# H05.net
KiCad netlist of a schematic drawn in EAGLE
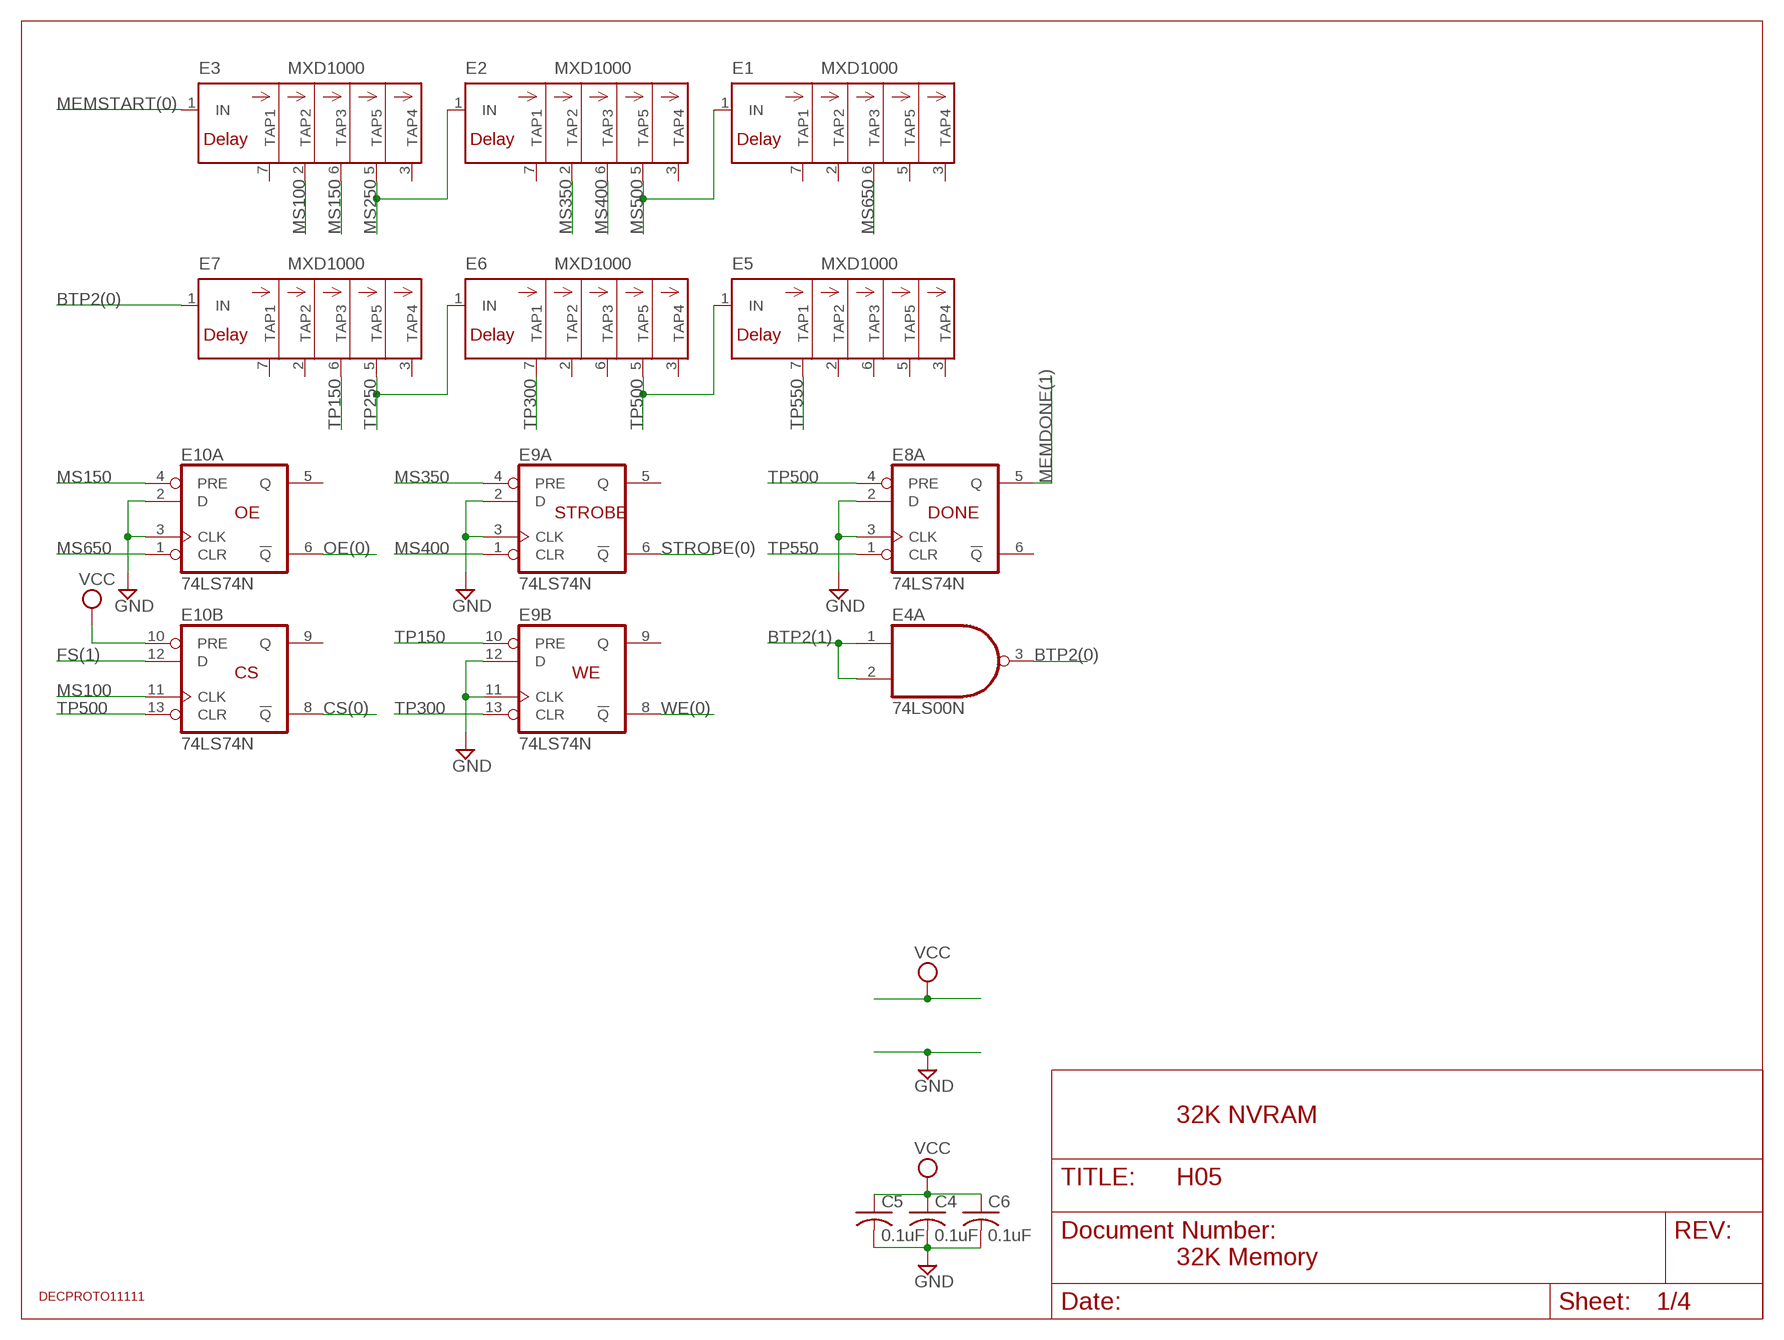
[diagram p0: schematic, sheet 1]
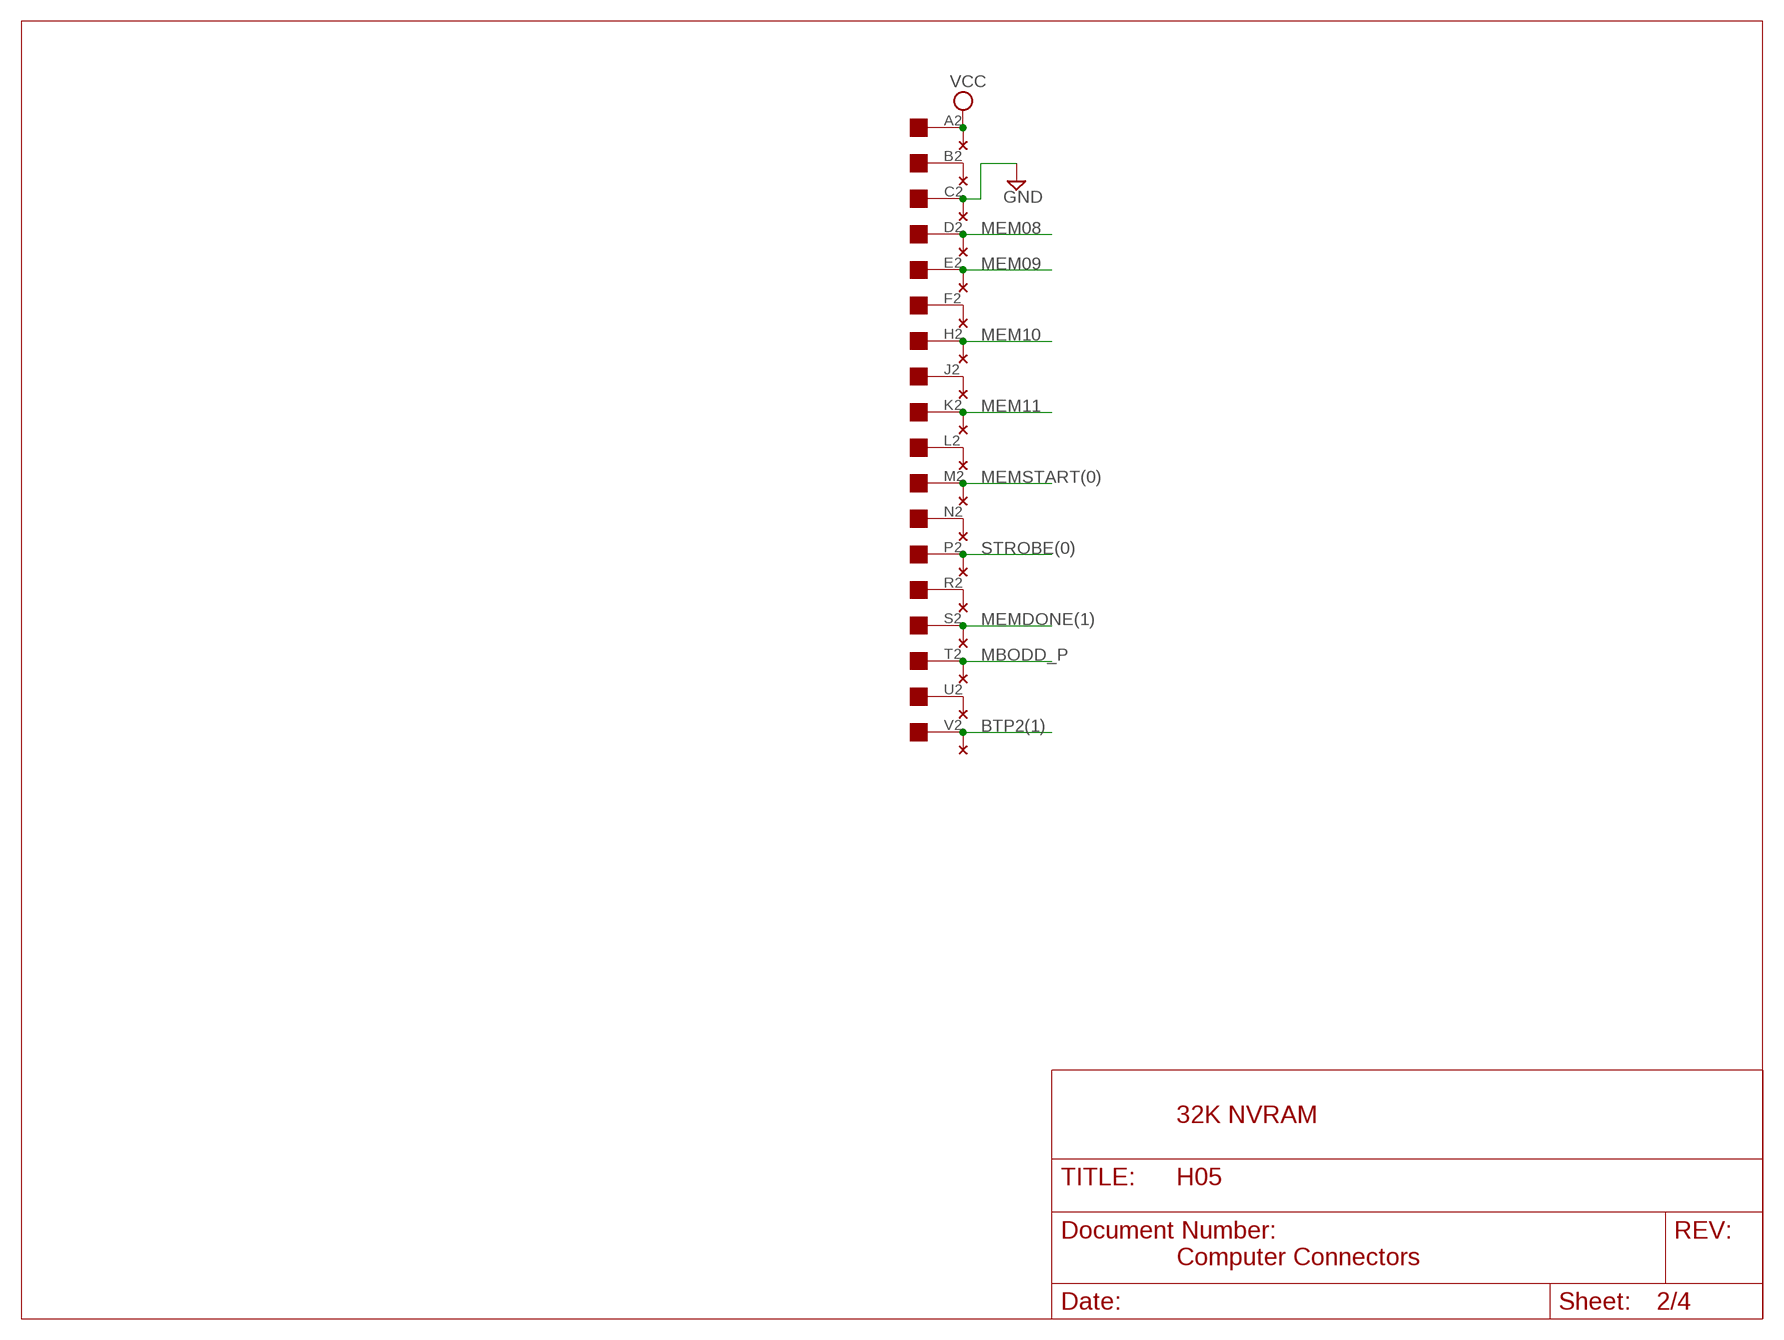
[diagram p1: schematic, sheet 2]
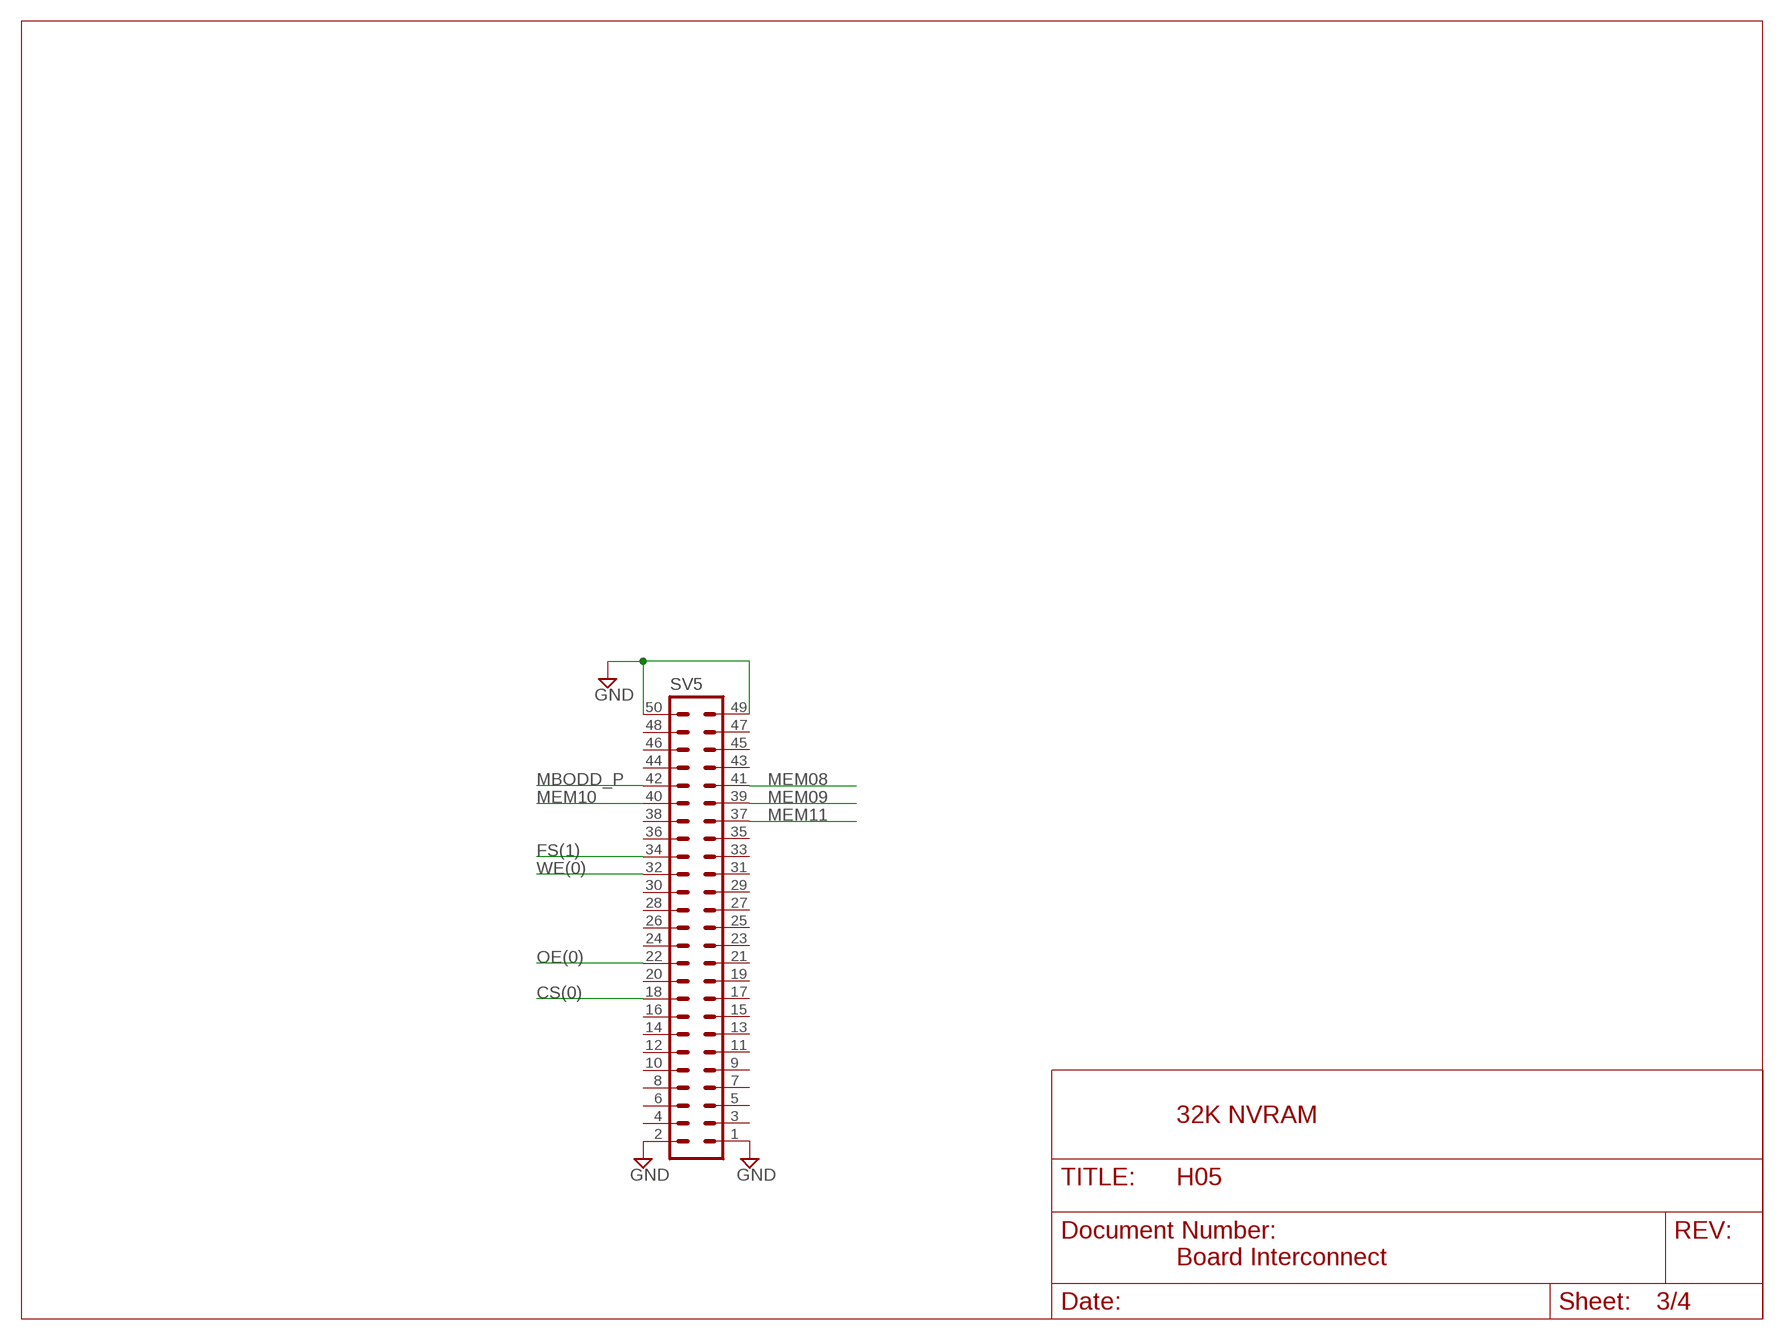
[diagram p2: schematic, sheet 3]
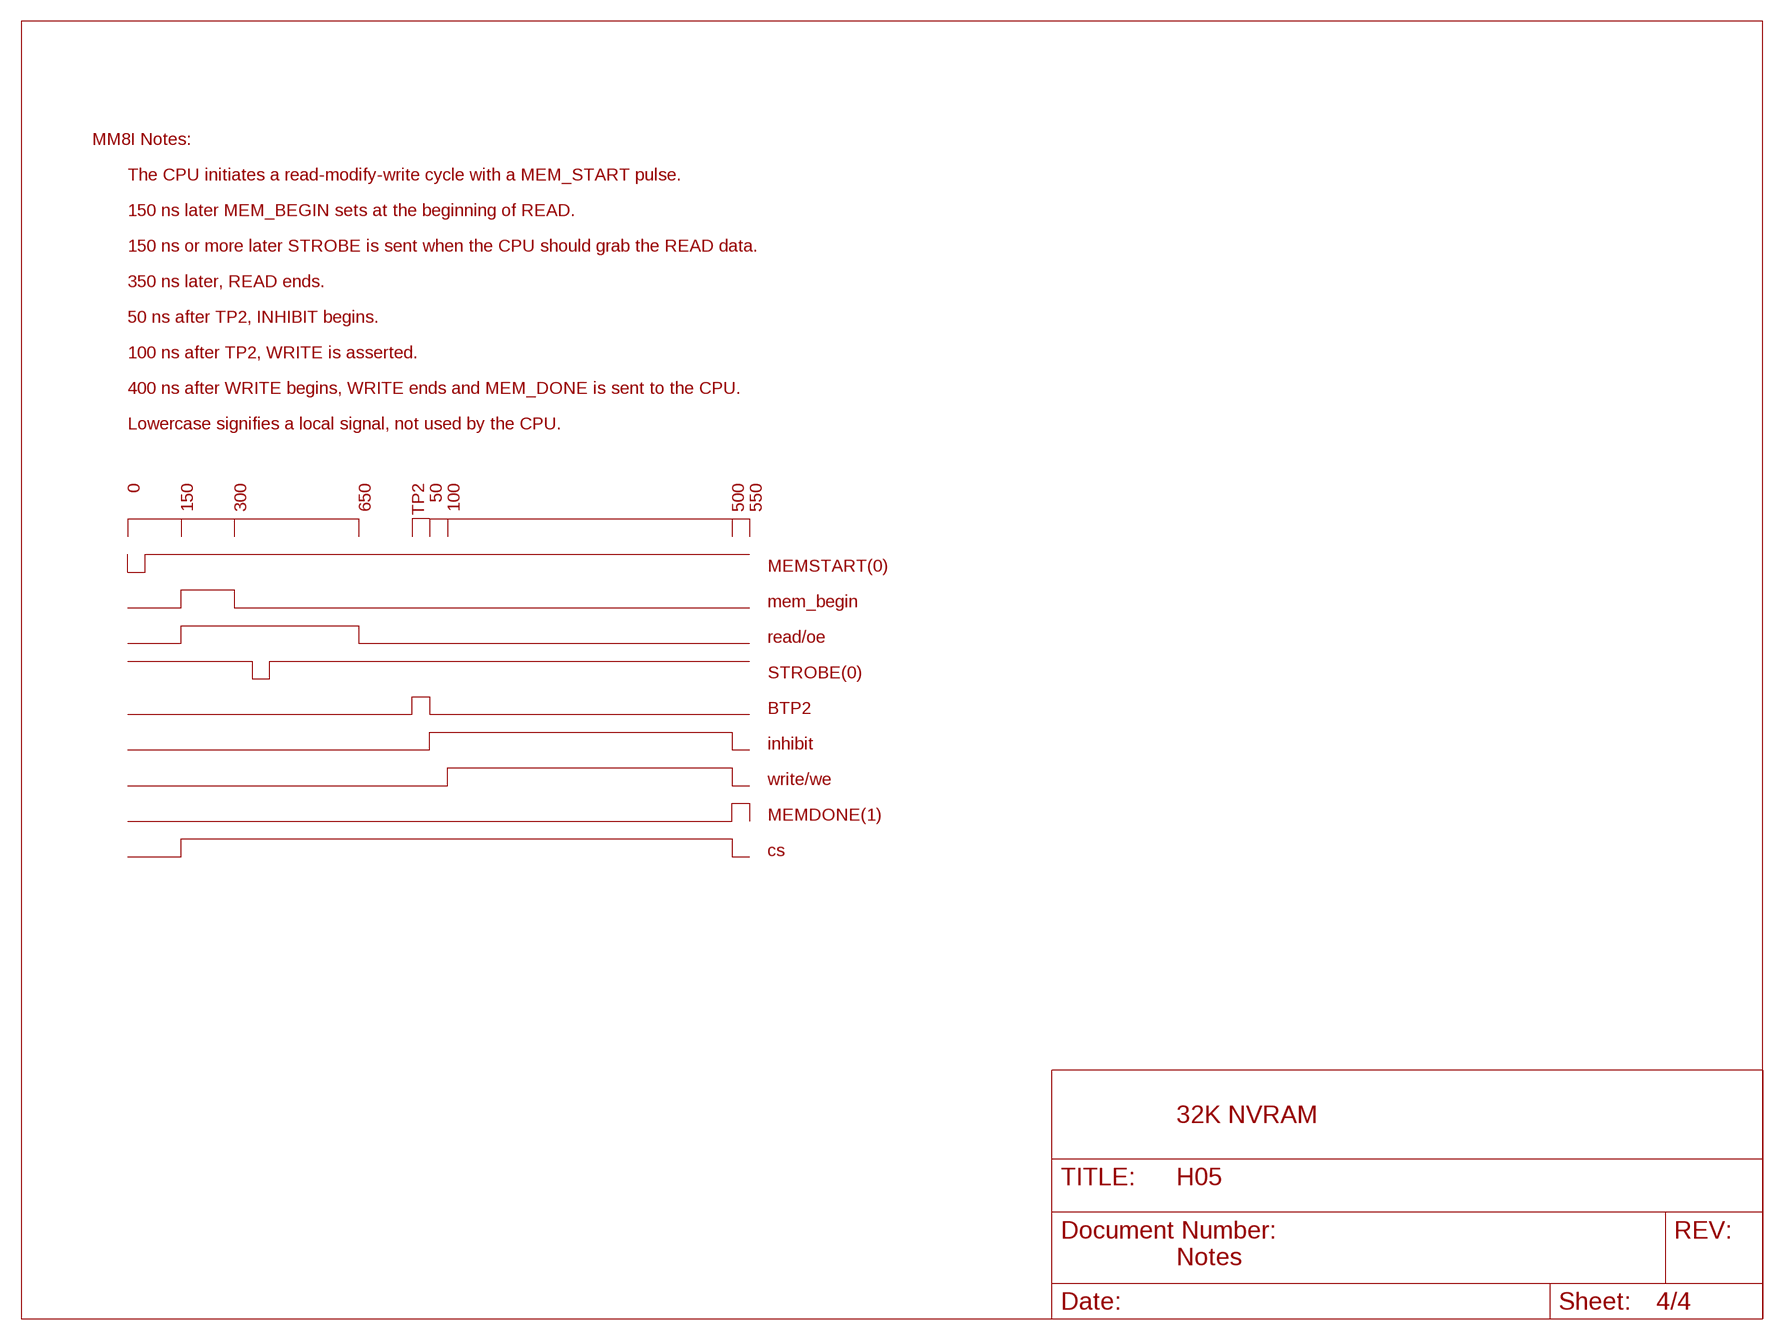
[diagram p3: schematic, sheet 4]

(export (version "E")
  (design (tool "Eeschema 10.0.6"))
  (components
    (comp (ref "H05")
      (value "EDGE-1")
      (footprint "eagle-import:EDGE-CON1")
      (libsource (lib "eagle-import") (part "EDGE-1"))
    )
    (comp (ref "U$5")
      (value "THRU-HOLE2")
      (footprint "eagle-import:THRU-HOLEB")
      (libsource (lib "eagle-import") (part "THRU-HOLE2"))
    )
    (comp (ref "C4")
      (value "0.1uF")
      (footprint "eagle-import:C050-025X075")
      (libsource (lib "eagle-import") (part "C-US050-025X075"))
    )
    (comp (ref "C5")
      (value "0.1uF")
      (footprint "eagle-import:C050-025X075")
      (libsource (lib "eagle-import") (part "C-US050-025X075"))
    )
    (comp (ref "C6")
      (value "0.1uF")
      (footprint "eagle-import:C050-025X075")
      (libsource (lib "eagle-import") (part "C-US050-025X075"))
    )
    (comp (ref "E1")
      (value "MXD1000")
      (footprint "eagle-import:DIL08")
      (libsource (lib "eagle-import") (part "MXD1000"))
    )
    (comp (ref "E2")
      (value "MXD1000")
      (footprint "eagle-import:DIL08")
      (libsource (lib "eagle-import") (part "MXD1000"))
    )
    (comp (ref "E3")
      (value "MXD1000")
      (footprint "eagle-import:DIL08")
      (libsource (lib "eagle-import") (part "MXD1000"))
    )
    (comp (ref "E4")
      (value "74LS00N")
      (footprint "eagle-import:DIL14")
      (libsource (lib "eagle-import") (part "7400NLS"))
    )
    (comp (ref "E5")
      (value "MXD1000")
      (footprint "eagle-import:DIL08")
      (libsource (lib "eagle-import") (part "MXD1000"))
    )
    (comp (ref "E6")
      (value "MXD1000")
      (footprint "eagle-import:DIL08")
      (libsource (lib "eagle-import") (part "MXD1000"))
    )
    (comp (ref "E7")
      (value "MXD1000")
      (footprint "eagle-import:DIL08")
      (libsource (lib "eagle-import") (part "MXD1000"))
    )
    (comp (ref "E8")
      (value "74LS74N")
      (footprint "eagle-import:DIL14")
      (libsource (lib "eagle-import") (part "7474NLS"))
    )
    (comp (ref "E9")
      (value "74LS74N")
      (footprint "eagle-import:DIL14")
      (libsource (lib "eagle-import") (part "7474NLS"))
    )
    (comp (ref "E10")
      (value "74LS74N")
      (footprint "eagle-import:DIL14")
      (libsource (lib "eagle-import") (part "7474NLS"))
    )
    (comp (ref "U$6")
      (value "DECPROTO11111")
      (footprint "eagle-import:DECPROTO11111")
      (libsource (lib "eagle-import") (part "DECPROTO11111"))
    )
    (comp (ref "SV5")
      (value "ML50L")
      (footprint "eagle-import:ML50L")
      (libsource (lib "eagle-import") (part "ML50L"))
    )
  )
  (nets
    (net (code "1") (name "BTP2(0)") (class "Default")
      (node (ref "E4") (pin "3") (pinfunction "O_3") (pintype "output"))
      (node (ref "E7") (pin "1") (pinfunction "IN_1") (pintype "input"))
    )
    (net (code "2") (name "BTP2(1)") (class "Default")
      (node (ref "E4") (pin "1") (pinfunction "I0_1") (pintype "input"))
      (node (ref "E4") (pin "2") (pinfunction "I1_2") (pintype "input"))
      (node (ref "H05") (pin "V2") (pinfunction "1_V2") (pintype "bidirectional"))
      (node (ref "U$5") (pin "V2") (pinfunction "P$1_V2") (pintype "passive"))
    )
    (net (code "3") (name "CS(0)") (class "Default")
      (node (ref "E10") (pin "8") (pinfunction "~{Q}_8") (pintype "output"))
      (node (ref "SV5") (pin "18") (pinfunction "18_18") (pintype "passive"))
    )
    (net (code "4") (name "FS(1)") (class "Default")
      (node (ref "E10") (pin "12") (pinfunction "D_12") (pintype "input"))
      (node (ref "SV5") (pin "34") (pinfunction "34_34") (pintype "passive"))
    )
    (net (code "5") (name "GND") (class "Default")
      (node (ref "C4") (pin "2") (pinfunction "2_2") (pintype "passive"))
      (node (ref "C5") (pin "2") (pinfunction "2_2") (pintype "passive"))
      (node (ref "C6") (pin "2") (pinfunction "2_2") (pintype "passive"))
      (node (ref "E10") (pin "2") (pinfunction "D_2") (pintype "input"))
      (node (ref "E10") (pin "3") (pinfunction "CLK_3") (pintype "input"))
      (node (ref "E8") (pin "2") (pinfunction "D_2") (pintype "input"))
      (node (ref "E8") (pin "3") (pinfunction "CLK_3") (pintype "input"))
      (node (ref "E9") (pin "11") (pinfunction "CLK_11") (pintype "input"))
      (node (ref "E9") (pin "12") (pinfunction "D_12") (pintype "input"))
      (node (ref "E9") (pin "2") (pinfunction "D_2") (pintype "input"))
      (node (ref "E9") (pin "3") (pinfunction "CLK_3") (pintype "input"))
      (node (ref "H05") (pin "C2") (pinfunction "1_C2") (pintype "bidirectional"))
      (node (ref "SV5") (pin "1") (pinfunction "1_1") (pintype "passive"))
      (node (ref "SV5") (pin "2") (pinfunction "2_2") (pintype "passive"))
      (node (ref "SV5") (pin "49") (pinfunction "49_49") (pintype "passive"))
      (node (ref "SV5") (pin "50") (pinfunction "50_50") (pintype "passive"))
      (node (ref "U$5") (pin "C2") (pinfunction "P$1_C2") (pintype "passive"))
    )
    (net (code "6") (name "MBODD_P") (class "Default")
      (node (ref "H05") (pin "T2") (pinfunction "1_T2") (pintype "bidirectional"))
      (node (ref "SV5") (pin "42") (pinfunction "42_42") (pintype "passive"))
      (node (ref "U$5") (pin "T2") (pinfunction "P$1_T2") (pintype "passive"))
    )
    (net (code "7") (name "MEM08") (class "Default")
      (node (ref "H05") (pin "D2") (pinfunction "1_D2") (pintype "bidirectional"))
      (node (ref "SV5") (pin "41") (pinfunction "41_41") (pintype "passive"))
      (node (ref "U$5") (pin "D2") (pinfunction "P$1_D2") (pintype "passive"))
    )
    (net (code "8") (name "MEM09") (class "Default")
      (node (ref "H05") (pin "E2") (pinfunction "1_E2") (pintype "bidirectional"))
      (node (ref "SV5") (pin "39") (pinfunction "39_39") (pintype "passive"))
      (node (ref "U$5") (pin "E2") (pinfunction "P$1_E2") (pintype "passive"))
    )
    (net (code "9") (name "MEM10") (class "Default")
      (node (ref "H05") (pin "H2") (pinfunction "1_H2") (pintype "bidirectional"))
      (node (ref "SV5") (pin "40") (pinfunction "40_40") (pintype "passive"))
      (node (ref "U$5") (pin "H2") (pinfunction "P$1_H2") (pintype "passive"))
    )
    (net (code "10") (name "MEM11") (class "Default")
      (node (ref "H05") (pin "K2") (pinfunction "1_K2") (pintype "bidirectional"))
      (node (ref "SV5") (pin "37") (pinfunction "37_37") (pintype "passive"))
      (node (ref "U$5") (pin "K2") (pinfunction "P$1_K2") (pintype "passive"))
    )
    (net (code "11") (name "MEMDONE(1)") (class "Default")
      (node (ref "E8") (pin "5") (pinfunction "Q_5") (pintype "output"))
      (node (ref "H05") (pin "S2") (pinfunction "1_S2") (pintype "bidirectional"))
      (node (ref "U$5") (pin "S2") (pinfunction "P$1_S2") (pintype "passive"))
    )
    (net (code "12") (name "MEMSTART(0)") (class "Default")
      (node (ref "E3") (pin "1") (pinfunction "IN_1") (pintype "input"))
      (node (ref "H05") (pin "M2") (pinfunction "1_M2") (pintype "bidirectional"))
      (node (ref "U$5") (pin "M2") (pinfunction "P$1_M2") (pintype "passive"))
    )
    (net (code "13") (name "MS100") (class "Default")
      (node (ref "E10") (pin "11") (pinfunction "CLK_11") (pintype "input"))
      (node (ref "E3") (pin "2") (pinfunction "TAP2_2") (pintype "output"))
    )
    (net (code "14") (name "MS150") (class "Default")
      (node (ref "E10") (pin "4") (pinfunction "PRE_4") (pintype "input"))
      (node (ref "E3") (pin "6") (pinfunction "TAP3_6") (pintype "output"))
    )
    (net (code "15") (name "MS250") (class "Default")
      (node (ref "E2") (pin "1") (pinfunction "IN_1") (pintype "input"))
      (node (ref "E3") (pin "5") (pinfunction "TAP5_5") (pintype "output"))
    )
    (net (code "16") (name "MS350") (class "Default")
      (node (ref "E2") (pin "2") (pinfunction "TAP2_2") (pintype "output"))
      (node (ref "E9") (pin "4") (pinfunction "PRE_4") (pintype "input"))
    )
    (net (code "17") (name "MS400") (class "Default")
      (node (ref "E2") (pin "6") (pinfunction "TAP3_6") (pintype "output"))
      (node (ref "E9") (pin "1") (pinfunction "CLR_1") (pintype "input"))
    )
    (net (code "18") (name "MS500") (class "Default")
      (node (ref "E1") (pin "1") (pinfunction "IN_1") (pintype "input"))
      (node (ref "E2") (pin "5") (pinfunction "TAP5_5") (pintype "output"))
    )
    (net (code "19") (name "MS650") (class "Default")
      (node (ref "E1") (pin "6") (pinfunction "TAP3_6") (pintype "output"))
      (node (ref "E10") (pin "1") (pinfunction "CLR_1") (pintype "input"))
    )
    (net (code "20") (name "Net-(H05B-1)") (class "Default")
      (node (ref "H05") (pin "B2") (pinfunction "1_B2") (pintype "bidirectional"))
      (node (ref "U$5") (pin "B2") (pinfunction "P$1_B2") (pintype "passive"))
    )
    (net (code "21") (name "Net-(H05F-1)") (class "Default")
      (node (ref "H05") (pin "F2") (pinfunction "1_F2") (pintype "bidirectional"))
      (node (ref "U$5") (pin "F2") (pinfunction "P$1_F2") (pintype "passive"))
    )
    (net (code "22") (name "Net-(H05H-1)") (class "Default")
      (node (ref "H05") (pin "J2") (pinfunction "1_J2") (pintype "bidirectional"))
      (node (ref "U$5") (pin "J2") (pinfunction "P$1_J2") (pintype "passive"))
    )
    (net (code "23") (name "Net-(H05J-1)") (class "Default")
      (node (ref "H05") (pin "L2") (pinfunction "1_L2") (pintype "bidirectional"))
      (node (ref "U$5") (pin "L2") (pinfunction "P$1_L2") (pintype "passive"))
    )
    (net (code "24") (name "Net-(H05L-1)") (class "Default")
      (node (ref "H05") (pin "N2") (pinfunction "1_N2") (pintype "bidirectional"))
      (node (ref "U$5") (pin "N2") (pinfunction "P$1_N2") (pintype "passive"))
    )
    (net (code "25") (name "Net-(H05N-1)") (class "Default")
      (node (ref "H05") (pin "R2") (pinfunction "1_R2") (pintype "bidirectional"))
      (node (ref "U$5") (pin "R2") (pinfunction "P$1_R2") (pintype "passive"))
    )
    (net (code "26") (name "Net-(H05Q-1)") (class "Default")
      (node (ref "H05") (pin "U2") (pinfunction "1_U2") (pintype "bidirectional"))
      (node (ref "U$5") (pin "U2") (pinfunction "P$1_U2") (pintype "passive"))
    )
    (net (code "27") (name "OE(0)") (class "Default")
      (node (ref "E10") (pin "6") (pinfunction "~{Q}_6") (pintype "output"))
      (node (ref "SV5") (pin "22") (pinfunction "22_22") (pintype "passive"))
    )
    (net (code "28") (name "STROBE(0)") (class "Default")
      (node (ref "E9") (pin "6") (pinfunction "~{Q}_6") (pintype "output"))
      (node (ref "H05") (pin "P2") (pinfunction "1_P2") (pintype "bidirectional"))
      (node (ref "U$5") (pin "P2") (pinfunction "P$1_P2") (pintype "passive"))
    )
    (net (code "29") (name "TP150") (class "Default")
      (node (ref "E7") (pin "6") (pinfunction "TAP3_6") (pintype "output"))
      (node (ref "E9") (pin "10") (pinfunction "PRE_10") (pintype "input"))
    )
    (net (code "30") (name "TP250") (class "Default")
      (node (ref "E6") (pin "1") (pinfunction "IN_1") (pintype "input"))
      (node (ref "E7") (pin "5") (pinfunction "TAP5_5") (pintype "output"))
    )
    (net (code "31") (name "TP300") (class "Default")
      (node (ref "E6") (pin "7") (pinfunction "TAP1_7") (pintype "output"))
      (node (ref "E9") (pin "13") (pinfunction "CLR_13") (pintype "input"))
    )
    (net (code "32") (name "TP500") (class "Default")
      (node (ref "E10") (pin "13") (pinfunction "CLR_13") (pintype "input"))
      (node (ref "E5") (pin "1") (pinfunction "IN_1") (pintype "input"))
      (node (ref "E6") (pin "5") (pinfunction "TAP5_5") (pintype "output"))
      (node (ref "E8") (pin "4") (pinfunction "PRE_4") (pintype "input"))
    )
    (net (code "33") (name "TP550") (class "Default")
      (node (ref "E5") (pin "7") (pinfunction "TAP1_7") (pintype "output"))
      (node (ref "E8") (pin "1") (pinfunction "CLR_1") (pintype "input"))
    )
    (net (code "34") (name "VCC") (class "Default")
      (node (ref "C4") (pin "1") (pinfunction "1_1") (pintype "passive"))
      (node (ref "C5") (pin "1") (pinfunction "1_1") (pintype "passive"))
      (node (ref "C6") (pin "1") (pinfunction "1_1") (pintype "passive"))
      (node (ref "E10") (pin "10") (pinfunction "PRE_10") (pintype "input"))
      (node (ref "H05") (pin "A2") (pinfunction "1_A2") (pintype "bidirectional"))
      (node (ref "U$5") (pin "A2") (pinfunction "P$1_A2") (pintype "passive"))
    )
    (net (code "35") (name "WE(0)") (class "Default")
      (node (ref "E9") (pin "8") (pinfunction "~{Q}_8") (pintype "output"))
      (node (ref "SV5") (pin "32") (pinfunction "32_32") (pintype "passive"))
    )
    (net (code "36") (name "unconnected-(E1A-TAP1-Pad7)") (class "Default")
      (node (ref "E1") (pin "7") (pinfunction "TAP1_7") (pintype "output"))
    )
    (net (code "37") (name "unconnected-(E1A-TAP2-Pad2)") (class "Default")
      (node (ref "E1") (pin "2") (pinfunction "TAP2_2") (pintype "output"))
    )
    (net (code "38") (name "unconnected-(E1A-TAP4-Pad3)") (class "Default")
      (node (ref "E1") (pin "3") (pinfunction "TAP4_3") (pintype "output"))
    )
    (net (code "39") (name "unconnected-(E1A-TAP5-Pad5)") (class "Default")
      (node (ref "E1") (pin "5") (pinfunction "TAP5_5") (pintype "output"))
    )
    (net (code "40") (name "unconnected-(E2A-TAP1-Pad7)") (class "Default")
      (node (ref "E2") (pin "7") (pinfunction "TAP1_7") (pintype "output"))
    )
    (net (code "41") (name "unconnected-(E2A-TAP4-Pad3)") (class "Default")
      (node (ref "E2") (pin "3") (pinfunction "TAP4_3") (pintype "output"))
    )
    (net (code "42") (name "unconnected-(E3A-TAP1-Pad7)") (class "Default")
      (node (ref "E3") (pin "7") (pinfunction "TAP1_7") (pintype "output"))
    )
    (net (code "43") (name "unconnected-(E3A-TAP4-Pad3)") (class "Default")
      (node (ref "E3") (pin "3") (pinfunction "TAP4_3") (pintype "output"))
    )
    (net (code "44") (name "unconnected-(E5A-TAP2-Pad2)") (class "Default")
      (node (ref "E5") (pin "2") (pinfunction "TAP2_2") (pintype "output"))
    )
    (net (code "45") (name "unconnected-(E5A-TAP3-Pad6)") (class "Default")
      (node (ref "E5") (pin "6") (pinfunction "TAP3_6") (pintype "output"))
    )
    (net (code "46") (name "unconnected-(E5A-TAP4-Pad3)") (class "Default")
      (node (ref "E5") (pin "3") (pinfunction "TAP4_3") (pintype "output"))
    )
    (net (code "47") (name "unconnected-(E5A-TAP5-Pad5)") (class "Default")
      (node (ref "E5") (pin "5") (pinfunction "TAP5_5") (pintype "output"))
    )
    (net (code "48") (name "unconnected-(E6A-TAP2-Pad2)") (class "Default")
      (node (ref "E6") (pin "2") (pinfunction "TAP2_2") (pintype "output"))
    )
    (net (code "49") (name "unconnected-(E6A-TAP3-Pad6)") (class "Default")
      (node (ref "E6") (pin "6") (pinfunction "TAP3_6") (pintype "output"))
    )
    (net (code "50") (name "unconnected-(E6A-TAP4-Pad3)") (class "Default")
      (node (ref "E6") (pin "3") (pinfunction "TAP4_3") (pintype "output"))
    )
    (net (code "51") (name "unconnected-(E7A-TAP1-Pad7)") (class "Default")
      (node (ref "E7") (pin "7") (pinfunction "TAP1_7") (pintype "output"))
    )
    (net (code "52") (name "unconnected-(E7A-TAP2-Pad2)") (class "Default")
      (node (ref "E7") (pin "2") (pinfunction "TAP2_2") (pintype "output"))
    )
    (net (code "53") (name "unconnected-(E7A-TAP4-Pad3)") (class "Default")
      (node (ref "E7") (pin "3") (pinfunction "TAP4_3") (pintype "output"))
    )
    (net (code "54") (name "unconnected-(E8A-~{Q}-Pad6)") (class "Default")
      (node (ref "E8") (pin "6") (pinfunction "~{Q}_6") (pintype "output"))
    )
    (net (code "55") (name "unconnected-(E9A-Q-Pad5)") (class "Default")
      (node (ref "E9") (pin "5") (pinfunction "Q_5") (pintype "output"))
    )
    (net (code "56") (name "unconnected-(E9B-Q-Pad9)") (class "Default")
      (node (ref "E9") (pin "9") (pinfunction "Q_9") (pintype "output"))
    )
    (net (code "57") (name "unconnected-(E10A-Q-Pad5)") (class "Default")
      (node (ref "E10") (pin "5") (pinfunction "Q_5") (pintype "output"))
    )
    (net (code "58") (name "unconnected-(E10B-Q-Pad9)") (class "Default")
      (node (ref "E10") (pin "9") (pinfunction "Q_9") (pintype "output"))
    )
    (net (code "59") (name "unconnected-(SV5-Pad3)") (class "Default")
      (node (ref "SV5") (pin "3") (pinfunction "3_3") (pintype "passive"))
    )
    (net (code "60") (name "unconnected-(SV5-Pad4)") (class "Default")
      (node (ref "SV5") (pin "4") (pinfunction "4_4") (pintype "passive"))
    )
    (net (code "61") (name "unconnected-(SV5-Pad5)") (class "Default")
      (node (ref "SV5") (pin "5") (pinfunction "5_5") (pintype "passive"))
    )
    (net (code "62") (name "unconnected-(SV5-Pad6)") (class "Default")
      (node (ref "SV5") (pin "6") (pinfunction "6_6") (pintype "passive"))
    )
    (net (code "63") (name "unconnected-(SV5-Pad7)") (class "Default")
      (node (ref "SV5") (pin "7") (pinfunction "7_7") (pintype "passive"))
    )
    (net (code "64") (name "unconnected-(SV5-Pad8)") (class "Default")
      (node (ref "SV5") (pin "8") (pinfunction "8_8") (pintype "passive"))
    )
    (net (code "65") (name "unconnected-(SV5-Pad9)") (class "Default")
      (node (ref "SV5") (pin "9") (pinfunction "9_9") (pintype "passive"))
    )
    (net (code "66") (name "unconnected-(SV5-Pad10)") (class "Default")
      (node (ref "SV5") (pin "10") (pinfunction "10_10") (pintype "passive"))
    )
    (net (code "67") (name "unconnected-(SV5-Pad11)") (class "Default")
      (node (ref "SV5") (pin "11") (pinfunction "11_11") (pintype "passive"))
    )
    (net (code "68") (name "unconnected-(SV5-Pad12)") (class "Default")
      (node (ref "SV5") (pin "12") (pinfunction "12_12") (pintype "passive"))
    )
    (net (code "69") (name "unconnected-(SV5-Pad13)") (class "Default")
      (node (ref "SV5") (pin "13") (pinfunction "13_13") (pintype "passive"))
    )
    (net (code "70") (name "unconnected-(SV5-Pad14)") (class "Default")
      (node (ref "SV5") (pin "14") (pinfunction "14_14") (pintype "passive"))
    )
    (net (code "71") (name "unconnected-(SV5-Pad15)") (class "Default")
      (node (ref "SV5") (pin "15") (pinfunction "15_15") (pintype "passive"))
    )
    (net (code "72") (name "unconnected-(SV5-Pad16)") (class "Default")
      (node (ref "SV5") (pin "16") (pinfunction "16_16") (pintype "passive"))
    )
    (net (code "73") (name "unconnected-(SV5-Pad17)") (class "Default")
      (node (ref "SV5") (pin "17") (pinfunction "17_17") (pintype "passive"))
    )
    (net (code "74") (name "unconnected-(SV5-Pad19)") (class "Default")
      (node (ref "SV5") (pin "19") (pinfunction "19_19") (pintype "passive"))
    )
    (net (code "75") (name "unconnected-(SV5-Pad20)") (class "Default")
      (node (ref "SV5") (pin "20") (pinfunction "20_20") (pintype "passive"))
    )
    (net (code "76") (name "unconnected-(SV5-Pad21)") (class "Default")
      (node (ref "SV5") (pin "21") (pinfunction "21_21") (pintype "passive"))
    )
    (net (code "77") (name "unconnected-(SV5-Pad23)") (class "Default")
      (node (ref "SV5") (pin "23") (pinfunction "23_23") (pintype "passive"))
    )
    (net (code "78") (name "unconnected-(SV5-Pad24)") (class "Default")
      (node (ref "SV5") (pin "24") (pinfunction "24_24") (pintype "passive"))
    )
    (net (code "79") (name "unconnected-(SV5-Pad25)") (class "Default")
      (node (ref "SV5") (pin "25") (pinfunction "25_25") (pintype "passive"))
    )
    (net (code "80") (name "unconnected-(SV5-Pad26)") (class "Default")
      (node (ref "SV5") (pin "26") (pinfunction "26_26") (pintype "passive"))
    )
    (net (code "81") (name "unconnected-(SV5-Pad27)") (class "Default")
      (node (ref "SV5") (pin "27") (pinfunction "27_27") (pintype "passive"))
    )
    (net (code "82") (name "unconnected-(SV5-Pad28)") (class "Default")
      (node (ref "SV5") (pin "28") (pinfunction "28_28") (pintype "passive"))
    )
    (net (code "83") (name "unconnected-(SV5-Pad29)") (class "Default")
      (node (ref "SV5") (pin "29") (pinfunction "29_29") (pintype "passive"))
    )
    (net (code "84") (name "unconnected-(SV5-Pad30)") (class "Default")
      (node (ref "SV5") (pin "30") (pinfunction "30_30") (pintype "passive"))
    )
    (net (code "85") (name "unconnected-(SV5-Pad31)") (class "Default")
      (node (ref "SV5") (pin "31") (pinfunction "31_31") (pintype "passive"))
    )
    (net (code "86") (name "unconnected-(SV5-Pad33)") (class "Default")
      (node (ref "SV5") (pin "33") (pinfunction "33_33") (pintype "passive"))
    )
    (net (code "87") (name "unconnected-(SV5-Pad35)") (class "Default")
      (node (ref "SV5") (pin "35") (pinfunction "35_35") (pintype "passive"))
    )
    (net (code "88") (name "unconnected-(SV5-Pad36)") (class "Default")
      (node (ref "SV5") (pin "36") (pinfunction "36_36") (pintype "passive"))
    )
    (net (code "89") (name "unconnected-(SV5-Pad38)") (class "Default")
      (node (ref "SV5") (pin "38") (pinfunction "38_38") (pintype "passive"))
    )
    (net (code "90") (name "unconnected-(SV5-Pad43)") (class "Default")
      (node (ref "SV5") (pin "43") (pinfunction "43_43") (pintype "passive"))
    )
    (net (code "91") (name "unconnected-(SV5-Pad44)") (class "Default")
      (node (ref "SV5") (pin "44") (pinfunction "44_44") (pintype "passive"))
    )
    (net (code "92") (name "unconnected-(SV5-Pad45)") (class "Default")
      (node (ref "SV5") (pin "45") (pinfunction "45_45") (pintype "passive"))
    )
    (net (code "93") (name "unconnected-(SV5-Pad46)") (class "Default")
      (node (ref "SV5") (pin "46") (pinfunction "46_46") (pintype "passive"))
    )
    (net (code "94") (name "unconnected-(SV5-Pad47)") (class "Default")
      (node (ref "SV5") (pin "47") (pinfunction "47_47") (pintype "passive"))
    )
    (net (code "95") (name "unconnected-(SV5-Pad48)") (class "Default")
      (node (ref "SV5") (pin "48") (pinfunction "48_48") (pintype "passive"))
    )
  )
)
